# XQ8266.net
KiCad netlist of a schematic drawn in EasyEDA Pro
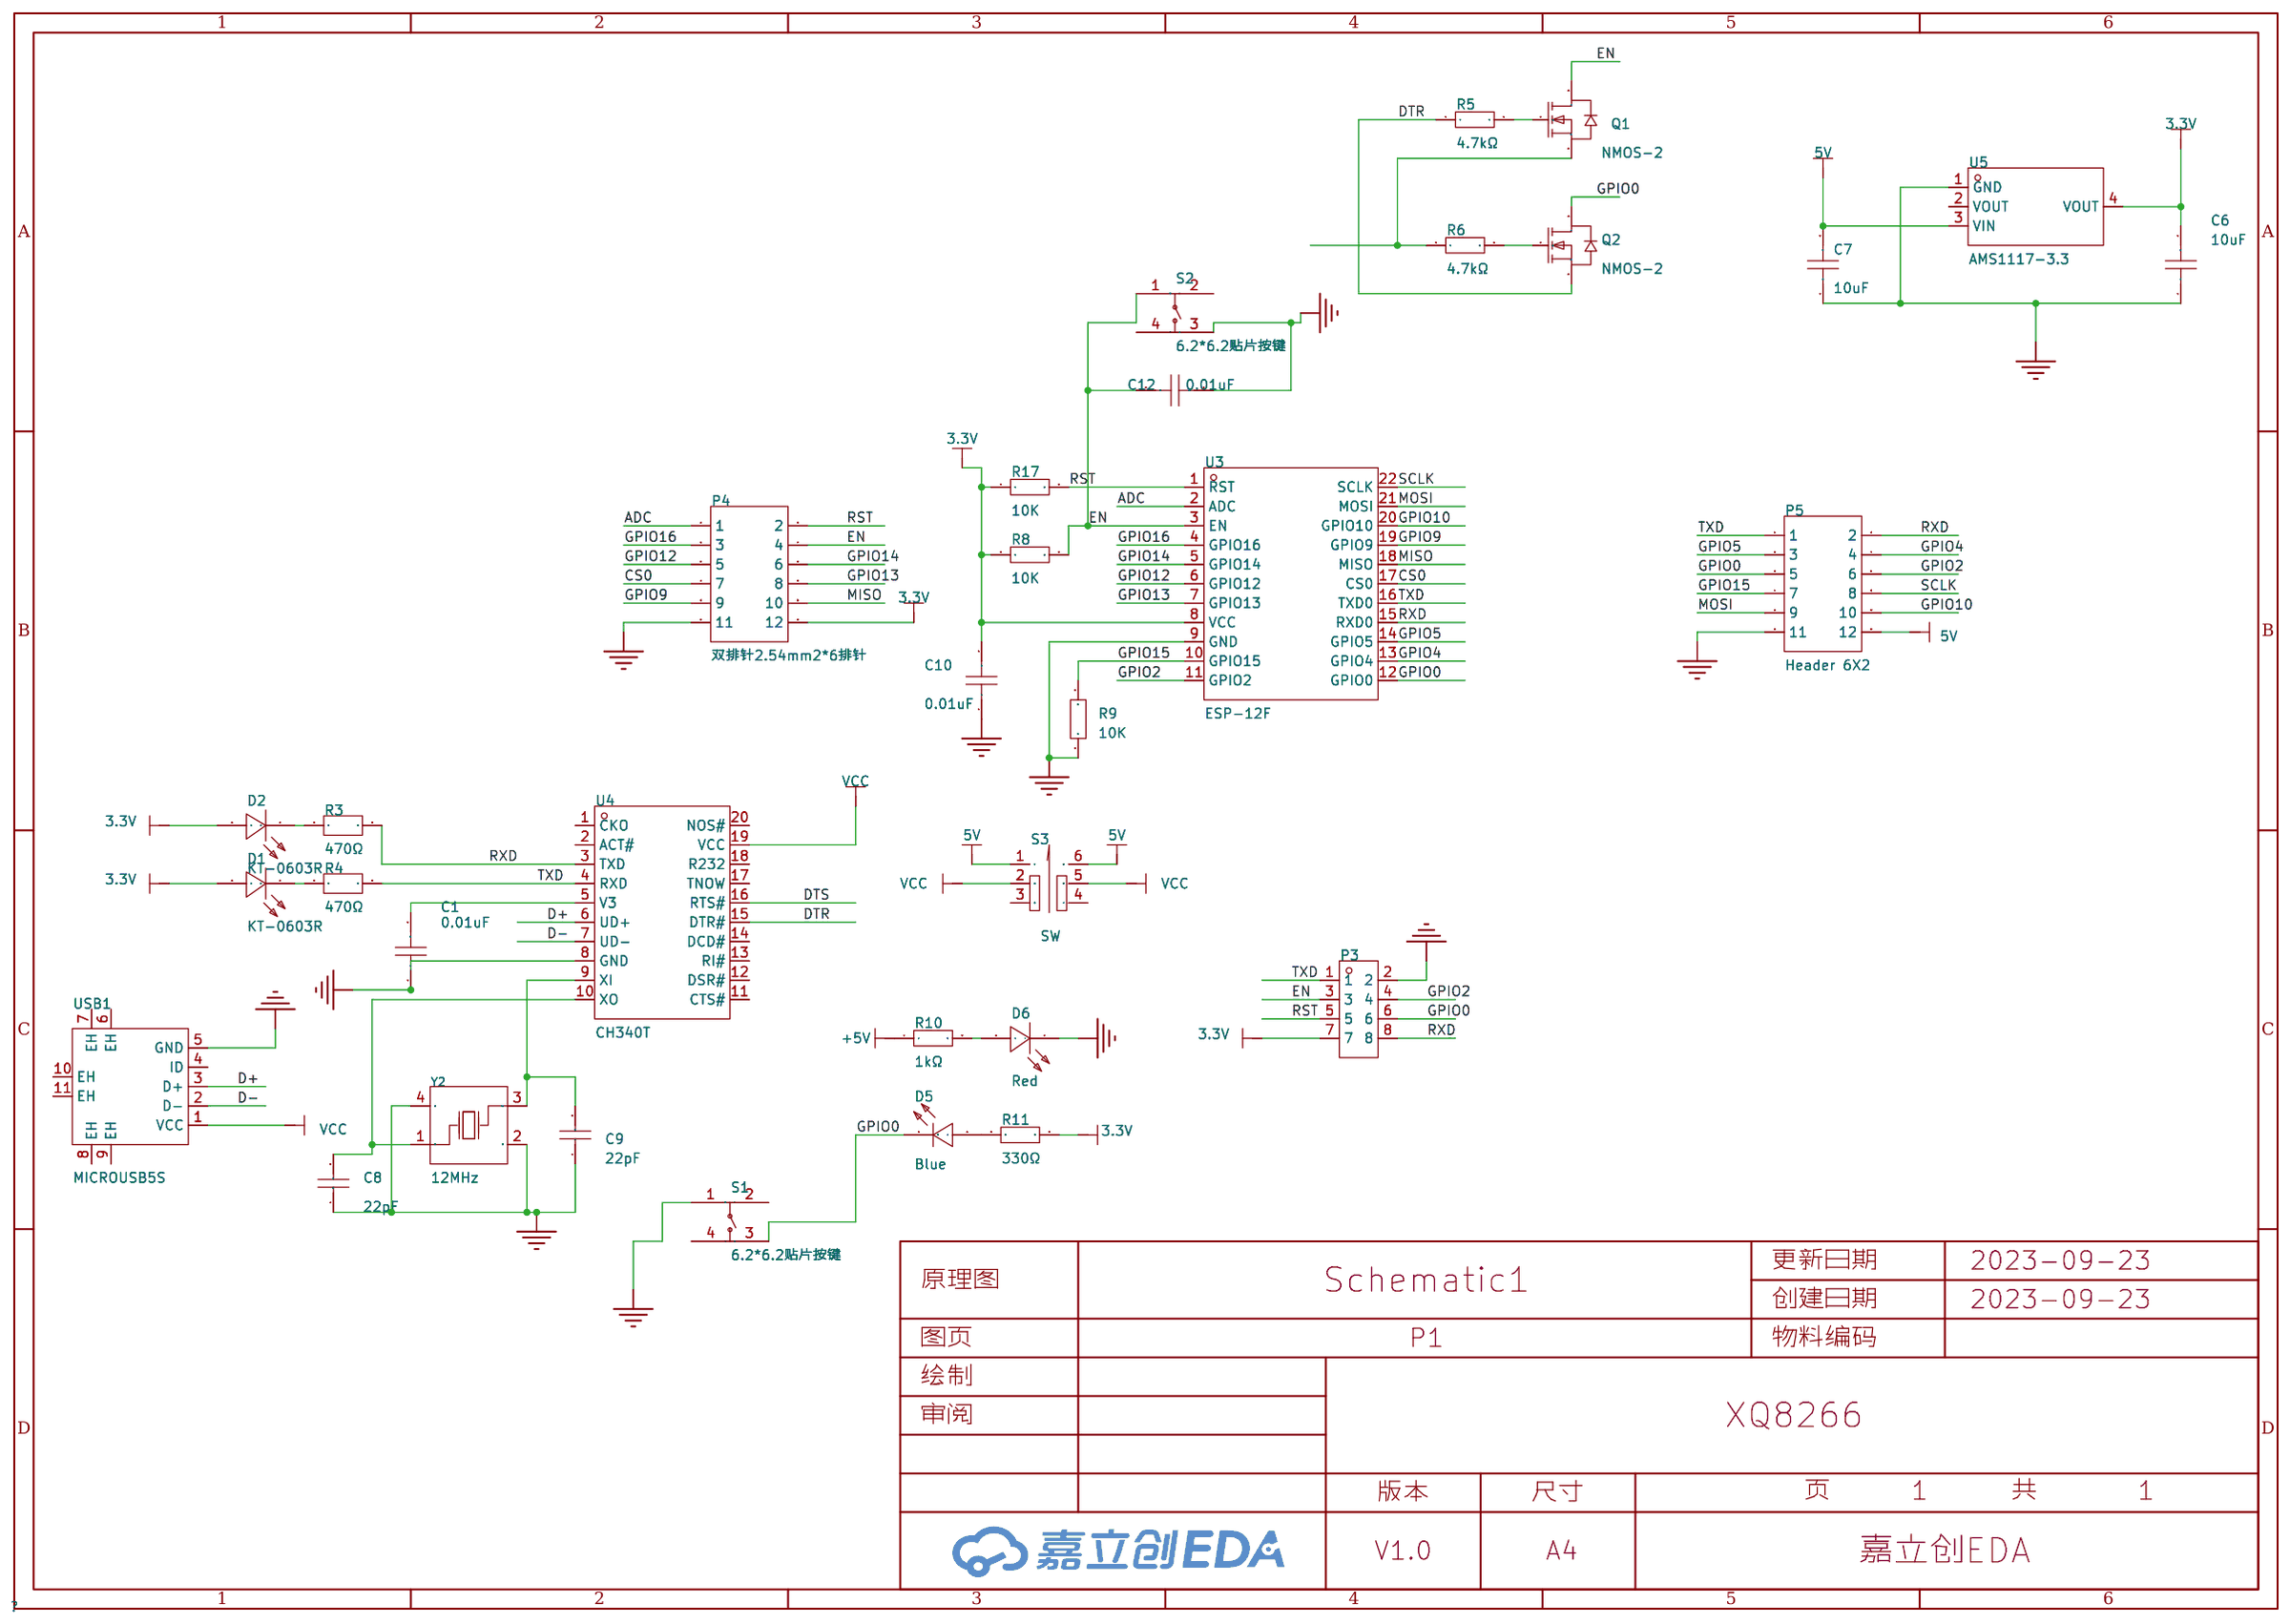
[diagram p0: schematic sheet]

(export (version "E")
  (design (tool "Eeschema 10.0.6"))
  (components
    (comp (ref "C1")
      (value "0.01uF")
      (footprint "easyedapro:C0603")
      (description "精度:±10%;")
      (libsource (lib "easyedapro") (part "CT41-0603-2X1-50V-0.01UF-K(N)"))
    )
    (comp (ref "C6")
      (value "10uF")
      (footprint "easyedapro:C0603")
      (description "容值:10uF;精度:±20%;额定电压:16V;材质(温度系数):-;")
      (fields (field (name "Manufacturer") "SAMSUNG(三星)"))
      (libsource (lib "easyedapro") (part "10UF"))
    )
    (comp (ref "C7")
      (value "10uF")
      (footprint "easyedapro:C0603")
      (description "容值:10uF;精度:±20%;额定电压:16V;材质(温度系数):-;")
      (fields (field (name "Manufacturer") "SAMSUNG(三星)"))
      (libsource (lib "easyedapro") (part "10UF"))
    )
    (comp (ref "C8")
      (value "22pF")
      (footprint "easyedapro:C0603")
      (description "容值:22pF;精度:±5%;额定电压:50V;材质(温度系数):C0G;")
      (fields
        (field (name "Manufacturer Part") "CL10C220JB8NNNC")
        (field (name "Manufacturer") "SAMSUNG(三星)")
      )
      (libsource (lib "easyedapro") (part "CL10C220JB8NNNC"))
    )
    (comp (ref "C9")
      (value "22pF")
      (footprint "easyedapro:C0603")
      (description "容值:22pF;精度:±5%;额定电压:50V;材质(温度系数):C0G;")
      (fields
        (field (name "Manufacturer Part") "CL10C220JB8NNNC")
        (field (name "Manufacturer") "SAMSUNG(三星)")
      )
      (libsource (lib "easyedapro") (part "CL10C220JB8NNNC"))
    )
    (comp (ref "C10")
      (value "0.01uF")
      (footprint "easyedapro:C0603")
      (description "精度:±10%;")
      (libsource (lib "easyedapro") (part "CT41-0603-2X1-50V-0.01UF-K(N)"))
    )
    (comp (ref "C12")
      (value "0.01uF")
      (footprint "easyedapro:C0603")
      (description "精度:±10%;")
      (libsource (lib "easyedapro") (part "CT41-0603-2X1-50V-0.01UF-K(N)"))
    )
    (comp (ref "D1")
      (value "KT-0603R")
      (footprint "easyedapro:LED0603-RD")
      (description "发光颜色:红灯;二极管配置:-;透镜颜色:-;主波长:-;色温:-;功率:-;发光角度:-;安装方式:-;工作温度:-40°C~+85°C;")
      (fields (field (name "Manufacturer") "KENTO"))
      (libsource (lib "easyedapro") (part "KT-0603R"))
    )
    (comp (ref "D2")
      (value "KT-0603R")
      (footprint "easyedapro:LED0603-RD")
      (description "发光颜色:红灯;二极管配置:-;透镜颜色:-;主波长:-;色温:-;功率:-;发光角度:-;安装方式:-;工作温度:-40°C~+85°C;")
      (fields (field (name "Manufacturer") "KENTO"))
      (libsource (lib "easyedapro") (part "KT-0603R"))
    )
    (comp (ref "D5")
      (value "Blue")
      (footprint "easyedapro:LED0603-FD_BLUE")
      (description "发光颜色:蓝灯;二极管配置:-;主波长:465nm~475nm;色温:-;功率:110mW;安装方式:-;")
      (fields (field (name "Manufacturer") "EVERLIGHT(亿光)"))
      (libsource (lib "easyedapro") (part "19-217/BHC-ZL1M2RY/3T"))
    )
    (comp (ref "D6")
      (value "Red")
      (footprint "easyedapro:LED0603-RD")
      (libsource (lib "easyedapro") (part "LTE-C9908-GD"))
    )
    (comp (ref "P3")
      (value "2.0排针 2*4p")
      (footprint "easyedapro:HDR-TH_8P-P2.00-V-M-R2-C4-S2.00")
      (libsource (lib "easyedapro") (part "2.0排针 2*4P"))
    )
    (comp (ref "P4")
      (value "双排针2.54mm2*6排针")
      (footprint "easyedapro:HDR-TH_12P-P2.54-V-M-R2-C6-S2.54")
      (libsource (lib "easyedapro") (part "Header-Male-2.54_2x6"))
    )
    (comp (ref "P5")
      (value "Header 6X2")
      (footprint "easyedapro:HDR-TH_12P-P2.54-V-M-R2-C6-S2.54")
      (libsource (lib "easyedapro") (part "Header-Male-2.54_2x6"))
    )
    (comp (ref "Q1")
      (value "NMOS-2")
      (footprint "easyedapro:SOT-323-3_L2.0-W1.3-P1.30-LS2.1-BR")
      (libsource (lib "easyedapro") (part "NMOS-2"))
    )
    (comp (ref "Q2")
      (value "NMOS-2")
      (footprint "easyedapro:SOT-323-3_L2.0-W1.3-P1.30-LS2.1-BR")
      (libsource (lib "easyedapro") (part "NMOS-2"))
    )
    (comp (ref "R3")
      (value "470Ω")
      (footprint "easyedapro:R0603")
      (description "阻值:470Ω;精度:±1%;功率:100mW;")
      (fields
        (field (name "Manufacturer Part") "CR0603F470RP05Z")
        (field (name "Manufacturer") "EVER OHMS(天二科技)")
      )
      (libsource (lib "easyedapro") (part "CR0603F470RP05Z"))
    )
    (comp (ref "R4")
      (value "470Ω")
      (footprint "easyedapro:R0603")
      (description "阻值:470Ω;精度:±1%;功率:100mW;")
      (fields
        (field (name "Manufacturer Part") "CR0603F470RP05Z")
        (field (name "Manufacturer") "EVER OHMS(天二科技)")
      )
      (libsource (lib "easyedapro") (part "CR0603F470RP05Z"))
    )
    (comp (ref "R5")
      (value "4.7kΩ")
      (footprint "easyedapro:R0603")
      (description "电阻类型:厚膜电阻;阻值:4.7kΩ;精度:±1%;功率:100mW;")
      (fields
        (field (name "Manufacturer Part") "0603WAF4701T5E")
        (field (name "Manufacturer") "UNI-ROYAL(厚声)")
      )
      (libsource (lib "easyedapro") (part "0603WAF4701T5E"))
    )
    (comp (ref "R6")
      (value "4.7kΩ")
      (footprint "easyedapro:R0603")
      (description "电阻类型:厚膜电阻;阻值:4.7kΩ;精度:±1%;功率:100mW;")
      (fields
        (field (name "Manufacturer Part") "0603WAF4701T5E")
        (field (name "Manufacturer") "UNI-ROYAL(厚声)")
      )
      (libsource (lib "easyedapro") (part "0603WAF4701T5E"))
    )
    (comp (ref "R8")
      (value "10K")
      (footprint "easyedapro:R0603")
      (description "电阻类型:厚膜电阻;阻值:10kΩ;精度:±1%;功率:100mW;")
      (fields
        (field (name "Manufacturer Part") "0603WAF1002T5E")
        (field (name "Manufacturer") "UNI-ROYAL(厚声)")
      )
      (libsource (lib "easyedapro") (part "0603WAF1002T5E"))
    )
    (comp (ref "R9")
      (value "10K")
      (footprint "easyedapro:R0603")
      (description "电阻类型:厚膜电阻;阻值:10kΩ;精度:±1%;功率:100mW;")
      (fields
        (field (name "Manufacturer Part") "0603WAF1002T5E")
        (field (name "Manufacturer") "UNI-ROYAL(厚声)")
      )
      (libsource (lib "easyedapro") (part "0603WAF1002T5E"))
    )
    (comp (ref "R10")
      (value "1kΩ")
      (footprint "easyedapro:R0603")
      (description "电阻类型:厚膜电阻;阻值:1kΩ;精度:±1%;功率:100mW;")
      (fields
        (field (name "Manufacturer Part") "0603WAF1001T5E")
        (field (name "Manufacturer") "UNI-ROYAL(厚声)")
      )
      (libsource (lib "easyedapro") (part "0603WAF1001T5E"))
    )
    (comp (ref "R11")
      (value "330Ω")
      (footprint "easyedapro:R0805")
      (description "电阻类型:厚膜电阻;阻值:330Ω;精度:±1%;功率:125mW;")
      (fields
        (field (name "Manufacturer Part") "0805W8F3300T5E")
        (field (name "Manufacturer") "UNI-ROYAL(厚声)")
      )
      (libsource (lib "easyedapro") (part "0805W8F3300T5E"))
    )
    (comp (ref "R17")
      (value "10K")
      (footprint "easyedapro:R0603")
      (description "电阻类型:厚膜电阻;阻值:10kΩ;精度:±1%;功率:100mW;")
      (fields
        (field (name "Manufacturer Part") "0603WAF1002T5E")
        (field (name "Manufacturer") "UNI-ROYAL(厚声)")
      )
      (libsource (lib "easyedapro") (part "0603WAF1002T5E"))
    )
    (comp (ref "S1")
      (value "6.2*6.2贴片按键")
      (footprint "easyedapro:SW-SMD_4P-L6.2-W6.2-P4.00-LS9.5-TL")
      (libsource (lib "easyedapro") (part "6.2*6.2贴片按键"))
    )
    (comp (ref "S2")
      (value "6.2*6.2贴片按键")
      (footprint "easyedapro:SW-SMD_4P-L6.2-W6.2-P4.00-LS9.5-TL")
      (libsource (lib "easyedapro") (part "6.2*6.2贴片按键"))
    )
    (comp (ref "S3")
      (value "SW")
      (footprint "easyedapro:SW-TH_6P-L5.8-W5.8-P2.00-LS4.5-TR")
      (description "耐温260度")
      (libsource (lib "easyedapro") (part "Self-locking switch 5.8ZWhite and white260G"))
    )
    (comp (ref "U3")
      (value "ESP-12F")
      (footprint "easyedapro:WIFIM-SMD_ESP-12F-ESP8266MOD")
      (description "频率:2.4GHz;发射功率:16dBm;核心处理器:ESP8266;天线形式:PCB 板载天线;接收灵敏度:-90dBm;")
      (fields
        (field (name "Manufacturer Part") "ESP-12F(ESP8266MOD)")
        (field (name "Manufacturer") "Ai-Thinker(安信可)")
      )
      (libsource (lib "easyedapro") (part "ESP-12F(ESP8266MOD)"))
    )
    (comp (ref "U4")
      (value "CH340T")
      (footprint "easyedapro:SSOP-20_L7.5-W5.2-P0.65-LS8.0-BL")
      (description "应用功能:收发器;接口协议:USB 2.0;数据速率:2Mbps;供电电压:3.3V；5V;")
      (fields (field (name "Manufacturer") "WCH(南京沁恒)"))
      (libsource (lib "easyedapro") (part "CH340T"))
    )
    (comp (ref "U5")
      (value "AMS1117-3.3")
      (footprint "easyedapro:SOT-223-3_L6.5-W3.4-P2.30-LS7.0-BR")
      (description "输出类型:固定;输出极性:正;最大输入电压:-;输出电压:3.3V;输出电流:1A;电源纹波抑制比(PSRR):72dB@(120Hz);")
      (fields (field (name "Manufacturer") "AMS"))
      (libsource (lib "easyedapro") (part "AMS1117-3.3"))
    )
    (comp (ref "USB1")
      (value "MICROUSB5S")
      (footprint "easyedapro:MICRO-USB_MICRO-USB-5S")
      (libsource (lib "easyedapro") (part "MICROUSB5S"))
    )
    (comp (ref "Y2")
      (value "12MHz")
      (footprint "easyedapro:OSC-SMD_4P-L3.2-W2.5-BL")
      (description "频率:12MHz;频率公差:±10ppm;负载电容:20pF;")
      (fields (field (name "Manufacturer Part") "X322512MSB4SI") (field (name "Manufacturer") "YXC(扬兴晶振)"))
      (libsource (lib "easyedapro") (part "X322512MSB4SI"))
    )
  )
  (nets
    (net (code "1") (name "+5V") (class "Default")
      (node (ref "R10") (pin "1") (pinfunction "1_1") (pintype "input"))
    )
    (net (code "2") (name "/ADC") (class "Default")
      (node (ref "P4") (pin "1") (pinfunction "1_1") (pintype "input"))
      (node (ref "U3") (pin "2") (pinfunction "ADC_2") (pintype "input"))
    )
    (net (code "3") (name "/CS0") (class "Default")
      (node (ref "P4") (pin "7") (pinfunction "7_7") (pintype "input"))
      (node (ref "U3") (pin "17") (pinfunction "CS0_17") (pintype "input"))
    )
    (net (code "4") (name "/D+") (class "Default")
      (node (ref "U4") (pin "6") (pinfunction "UD+_6") (pintype "input"))
      (node (ref "USB1") (pin "3") (pinfunction "D+_3") (pintype "input"))
    )
    (net (code "5") (name "/D-") (class "Default")
      (node (ref "U4") (pin "7") (pinfunction "UD-_7") (pintype "input"))
      (node (ref "USB1") (pin "2") (pinfunction "D-_2") (pintype "input"))
    )
    (net (code "6") (name "/DTR") (class "Default")
      (node (ref "Q2") (pin "2") (pinfunction "S_2") (pintype "input"))
      (node (ref "R5") (pin "1") (pinfunction "1_1") (pintype "input"))
      (node (ref "U4") (pin "15") (pinfunction "DTR#_15") (pintype "input"))
    )
    (net (code "7") (name "/DTS") (class "Default")
      (node (ref "U4") (pin "16") (pinfunction "RTS#_16") (pintype "input"))
    )
    (net (code "8") (name "/EN") (class "Default")
      (node (ref "C12") (pin "2") (pinfunction "2_2") (pintype "input"))
      (node (ref "P3") (pin "3") (pinfunction "3_3") (pintype "input"))
      (node (ref "P4") (pin "4") (pinfunction "4_4") (pintype "input"))
      (node (ref "Q1") (pin "3") (pinfunction "D_3") (pintype "input"))
      (node (ref "R8") (pin "2") (pinfunction "2_2") (pintype "input"))
      (node (ref "S2") (pin "1") (pinfunction "1_1") (pintype "input"))
      (node (ref "U3") (pin "3") (pinfunction "EN_3") (pintype "input"))
    )
    (net (code "9") (name "/GPIO0") (class "Default")
      (node (ref "D5") (pin "1") (pinfunction "C_1") (pintype "input"))
      (node (ref "P3") (pin "6") (pinfunction "6_6") (pintype "input"))
      (node (ref "P5") (pin "5") (pinfunction "5_5") (pintype "input"))
      (node (ref "Q2") (pin "3") (pinfunction "D_3") (pintype "input"))
      (node (ref "S1") (pin "3") (pinfunction "3_3") (pintype "input"))
      (node (ref "U3") (pin "12") (pinfunction "GPIO0_12") (pintype "input"))
    )
    (net (code "10") (name "/GPIO2") (class "Default")
      (node (ref "P3") (pin "4") (pinfunction "4_4") (pintype "input"))
      (node (ref "P5") (pin "6") (pinfunction "6_6") (pintype "input"))
      (node (ref "U3") (pin "11") (pinfunction "GPIO2_11") (pintype "input"))
    )
    (net (code "11") (name "/GPIO4") (class "Default")
      (node (ref "P5") (pin "4") (pinfunction "4_4") (pintype "input"))
      (node (ref "U3") (pin "13") (pinfunction "GPIO4_13") (pintype "input"))
    )
    (net (code "12") (name "/GPIO5") (class "Default")
      (node (ref "P5") (pin "3") (pinfunction "3_3") (pintype "input"))
      (node (ref "U3") (pin "14") (pinfunction "GPIO5_14") (pintype "input"))
    )
    (net (code "13") (name "/GPIO9") (class "Default")
      (node (ref "P4") (pin "9") (pinfunction "9_9") (pintype "input"))
      (node (ref "U3") (pin "19") (pinfunction "GPIO9_19") (pintype "input"))
    )
    (net (code "14") (name "/GPIO10") (class "Default")
      (node (ref "P5") (pin "10") (pinfunction "10_10") (pintype "input"))
      (node (ref "U3") (pin "20") (pinfunction "GPIO10_20") (pintype "input"))
    )
    (net (code "15") (name "/GPIO12") (class "Default")
      (node (ref "P4") (pin "5") (pinfunction "5_5") (pintype "input"))
      (node (ref "U3") (pin "6") (pinfunction "GPIO12_6") (pintype "input"))
    )
    (net (code "16") (name "/GPIO13") (class "Default")
      (node (ref "P4") (pin "8") (pinfunction "8_8") (pintype "input"))
      (node (ref "U3") (pin "7") (pinfunction "GPIO13_7") (pintype "input"))
    )
    (net (code "17") (name "/GPIO14") (class "Default")
      (node (ref "P4") (pin "6") (pinfunction "6_6") (pintype "input"))
      (node (ref "U3") (pin "5") (pinfunction "GPIO14_5") (pintype "input"))
    )
    (net (code "18") (name "/GPIO15") (class "Default")
      (node (ref "P5") (pin "7") (pinfunction "7_7") (pintype "input"))
      (node (ref "R9") (pin "2") (pinfunction "2_2") (pintype "input"))
      (node (ref "U3") (pin "10") (pinfunction "GPIO15_10") (pintype "input"))
    )
    (net (code "19") (name "/GPIO16") (class "Default")
      (node (ref "P4") (pin "3") (pinfunction "3_3") (pintype "input"))
      (node (ref "U3") (pin "4") (pinfunction "GPIO16_4") (pintype "input"))
    )
    (net (code "20") (name "/MISO") (class "Default")
      (node (ref "P4") (pin "10") (pinfunction "10_10") (pintype "input"))
      (node (ref "U3") (pin "18") (pinfunction "MISO_18") (pintype "input"))
    )
    (net (code "21") (name "/MOSI") (class "Default")
      (node (ref "P5") (pin "9") (pinfunction "9_9") (pintype "input"))
      (node (ref "U3") (pin "21") (pinfunction "MOSI_21") (pintype "input"))
    )
    (net (code "22") (name "/RST") (class "Default")
      (node (ref "P3") (pin "5") (pinfunction "5_5") (pintype "input"))
      (node (ref "P4") (pin "2") (pinfunction "2_2") (pintype "input"))
      (node (ref "R17") (pin "2") (pinfunction "2_2") (pintype "input"))
      (node (ref "U3") (pin "1") (pinfunction "RST_1") (pintype "input"))
    )
    (net (code "23") (name "/RXD") (class "Default")
      (node (ref "P3") (pin "8") (pinfunction "8_8") (pintype "input"))
      (node (ref "P5") (pin "2") (pinfunction "2_2") (pintype "input"))
      (node (ref "R3") (pin "2") (pinfunction "2_2") (pintype "input"))
      (node (ref "U3") (pin "15") (pinfunction "RXD0_15") (pintype "input"))
      (node (ref "U4") (pin "3") (pinfunction "TXD_3") (pintype "input"))
    )
    (net (code "24") (name "/SCLK") (class "Default")
      (node (ref "P5") (pin "8") (pinfunction "8_8") (pintype "input"))
      (node (ref "U3") (pin "22") (pinfunction "SCLK_22") (pintype "input"))
    )
    (net (code "25") (name "/TXD") (class "Default")
      (node (ref "P3") (pin "1") (pinfunction "1_1") (pintype "input"))
      (node (ref "P5") (pin "1") (pinfunction "1_1") (pintype "input"))
      (node (ref "R4") (pin "2") (pinfunction "2_2") (pintype "input"))
      (node (ref "U3") (pin "16") (pinfunction "TXD0_16") (pintype "input"))
      (node (ref "U4") (pin "4") (pinfunction "RXD_4") (pintype "input"))
    )
    (net (code "26") (name "3.3V") (class "Default")
      (node (ref "C10") (pin "2") (pinfunction "2_2") (pintype "input"))
      (node (ref "C6") (pin "2") (pinfunction "2_2") (pintype "input"))
      (node (ref "D1") (pin "2") (pinfunction "A_2") (pintype "input"))
      (node (ref "D2") (pin "2") (pinfunction "A_2") (pintype "input"))
      (node (ref "P3") (pin "7") (pinfunction "7_7") (pintype "input"))
      (node (ref "P4") (pin "12") (pinfunction "12_12") (pintype "input"))
      (node (ref "R11") (pin "2") (pinfunction "2_2") (pintype "input"))
      (node (ref "R17") (pin "1") (pinfunction "1_1") (pintype "input"))
      (node (ref "R8") (pin "1") (pinfunction "1_1") (pintype "input"))
      (node (ref "U3") (pin "8") (pinfunction "VCC_8") (pintype "input"))
      (node (ref "U5") (pin "4") (pinfunction "VOUT_4") (pintype "input"))
    )
    (net (code "27") (name "5V") (class "Default")
      (node (ref "C7") (pin "2") (pinfunction "2_2") (pintype "input"))
      (node (ref "P5") (pin "12") (pinfunction "12_12") (pintype "input"))
      (node (ref "S3") (pin "1") (pinfunction "1_1") (pintype "input"))
      (node (ref "S3") (pin "6") (pinfunction "6_6") (pintype "input"))
      (node (ref "U5") (pin "3") (pinfunction "VIN_3") (pintype "input"))
    )
    (net (code "28") (name "GND") (class "Default")
      (node (ref "C1") (pin "1") (pinfunction "1_1") (pintype "input"))
      (node (ref "C10") (pin "1") (pinfunction "1_1") (pintype "input"))
      (node (ref "C12") (pin "1") (pinfunction "1_1") (pintype "input"))
      (node (ref "C6") (pin "1") (pinfunction "1_1") (pintype "input"))
      (node (ref "C7") (pin "1") (pinfunction "1_1") (pintype "input"))
      (node (ref "C8") (pin "1") (pinfunction "1_1") (pintype "input"))
      (node (ref "C9") (pin "1") (pinfunction "1_1") (pintype "input"))
      (node (ref "D6") (pin "1") (pinfunction "-_1") (pintype "input"))
      (node (ref "P3") (pin "2") (pinfunction "2_2") (pintype "input"))
      (node (ref "P4") (pin "11") (pinfunction "11_11") (pintype "input"))
      (node (ref "P5") (pin "11") (pinfunction "11_11") (pintype "input"))
      (node (ref "R9") (pin "1") (pinfunction "1_1") (pintype "input"))
      (node (ref "S1") (pin "1") (pinfunction "1_1") (pintype "input"))
      (node (ref "S2") (pin "3") (pinfunction "3_3") (pintype "input"))
      (node (ref "U3") (pin "9") (pinfunction "GND_9") (pintype "input"))
      (node (ref "U4") (pin "8") (pinfunction "GND_8") (pintype "input"))
      (node (ref "U5") (pin "1") (pinfunction "GND_1") (pintype "input"))
      (node (ref "USB1") (pin "5") (pinfunction "GND_5") (pintype "input"))
      (node (ref "Y2") (pin "2") (pinfunction "GND_2") (pintype "input"))
      (node (ref "Y2") (pin "4") (pinfunction "GND_4") (pintype "input"))
    )
    (net (code "29") (name "Net-(D1-K)") (class "Default")
      (node (ref "D1") (pin "1") (pinfunction "K_1") (pintype "input"))
      (node (ref "R4") (pin "1") (pinfunction "1_1") (pintype "input"))
    )
    (net (code "30") (name "Net-(D2-K)") (class "Default")
      (node (ref "D2") (pin "1") (pinfunction "K_1") (pintype "input"))
      (node (ref "R3") (pin "1") (pinfunction "1_1") (pintype "input"))
    )
    (net (code "31") (name "Net-(D5-A)") (class "Default")
      (node (ref "D5") (pin "2") (pinfunction "A_2") (pintype "input"))
      (node (ref "R11") (pin "1") (pinfunction "1_1") (pintype "input"))
    )
    (net (code "32") (name "Net-(D6-+)") (class "Default")
      (node (ref "D6") (pin "2") (pinfunction "+_2") (pintype "input"))
      (node (ref "R10") (pin "2") (pinfunction "2_2") (pintype "input"))
    )
    (net (code "33") (name "Net-(Q1-G)") (class "Default")
      (node (ref "Q1") (pin "1") (pinfunction "G_1") (pintype "input"))
      (node (ref "R5") (pin "2") (pinfunction "2_2") (pintype "input"))
    )
    (net (code "34") (name "Net-(Q1-S)") (class "Default")
      (node (ref "Q1") (pin "2") (pinfunction "S_2") (pintype "input"))
      (node (ref "R6") (pin "1") (pinfunction "1_1") (pintype "input"))
    )
    (net (code "35") (name "Net-(Q2-G)") (class "Default")
      (node (ref "Q2") (pin "1") (pinfunction "G_1") (pintype "input"))
      (node (ref "R6") (pin "2") (pinfunction "2_2") (pintype "input"))
    )
    (net (code "36") (name "Net-(U4-V3)") (class "Default")
      (node (ref "C1") (pin "2") (pinfunction "2_2") (pintype "input"))
      (node (ref "U4") (pin "5") (pinfunction "V3_5") (pintype "input"))
    )
    (net (code "37") (name "Net-(U4-XI)") (class "Default")
      (node (ref "C9") (pin "2") (pinfunction "2_2") (pintype "input"))
      (node (ref "U4") (pin "9") (pinfunction "XI_9") (pintype "input"))
      (node (ref "Y2") (pin "3") (pinfunction "OSC2_3") (pintype "input"))
    )
    (net (code "38") (name "Net-(U4-XO)") (class "Default")
      (node (ref "C8") (pin "2") (pinfunction "2_2") (pintype "input"))
      (node (ref "U4") (pin "10") (pinfunction "XO_10") (pintype "input"))
      (node (ref "Y2") (pin "1") (pinfunction "OSC1_1") (pintype "input"))
    )
    (net (code "39") (name "VCC") (class "Default")
      (node (ref "S3") (pin "2") (pinfunction "2_2") (pintype "input"))
      (node (ref "S3") (pin "5") (pinfunction "5_5") (pintype "input"))
      (node (ref "U4") (pin "19") (pinfunction "VCC_19") (pintype "input"))
      (node (ref "USB1") (pin "1") (pinfunction "VCC_1") (pintype "input"))
    )
    (net (code "40") (name "unconnected-(S1-Pad2)") (class "Default")
      (node (ref "S1") (pin "2") (pinfunction "2_2") (pintype "input"))
    )
    (net (code "41") (name "unconnected-(S1-Pad4)") (class "Default")
      (node (ref "S1") (pin "4") (pinfunction "4_4") (pintype "input"))
    )
    (net (code "42") (name "unconnected-(S2-Pad2)") (class "Default")
      (node (ref "S2") (pin "2") (pinfunction "2_2") (pintype "input"))
    )
    (net (code "43") (name "unconnected-(S2-Pad4)") (class "Default")
      (node (ref "S2") (pin "4") (pinfunction "4_4") (pintype "input"))
    )
    (net (code "44") (name "unconnected-(S3-Pad3)") (class "Default")
      (node (ref "S3") (pin "3") (pinfunction "3_3") (pintype "input"))
    )
    (net (code "45") (name "unconnected-(S3-Pad4)") (class "Default")
      (node (ref "S3") (pin "4") (pinfunction "4_4") (pintype "input"))
    )
    (net (code "46") (name "unconnected-(U4-ACT#-Pad2)") (class "Default")
      (node (ref "U4") (pin "2") (pinfunction "ACT#_2") (pintype "input"))
    )
    (net (code "47") (name "unconnected-(U4-CKO-Pad1)") (class "Default")
      (node (ref "U4") (pin "1") (pinfunction "CKO_1") (pintype "input"))
    )
    (net (code "48") (name "unconnected-(U4-CTS#-Pad11)") (class "Default")
      (node (ref "U4") (pin "11") (pinfunction "CTS#_11") (pintype "input"))
    )
    (net (code "49") (name "unconnected-(U4-DCD#-Pad14)") (class "Default")
      (node (ref "U4") (pin "14") (pinfunction "DCD#_14") (pintype "input"))
    )
    (net (code "50") (name "unconnected-(U4-DSR#-Pad12)") (class "Default")
      (node (ref "U4") (pin "12") (pinfunction "DSR#_12") (pintype "input"))
    )
    (net (code "51") (name "unconnected-(U4-NOS#-Pad20)") (class "Default")
      (node (ref "U4") (pin "20") (pinfunction "NOS#_20") (pintype "input"))
    )
    (net (code "52") (name "unconnected-(U4-R232-Pad18)") (class "Default")
      (node (ref "U4") (pin "18") (pinfunction "R232_18") (pintype "input"))
    )
    (net (code "53") (name "unconnected-(U4-RI#-Pad13)") (class "Default")
      (node (ref "U4") (pin "13") (pinfunction "RI#_13") (pintype "input"))
    )
    (net (code "54") (name "unconnected-(U4-TNOW-Pad17)") (class "Default")
      (node (ref "U4") (pin "17") (pinfunction "TNOW_17") (pintype "input"))
    )
    (net (code "55") (name "unconnected-(U5-VOUT-Pad2)") (class "Default")
      (node (ref "U5") (pin "2") (pinfunction "VOUT_2") (pintype "input"))
    )
    (net (code "56") (name "unconnected-(USB1-EH-Pad6)") (class "Default")
      (node (ref "USB1") (pin "6") (pinfunction "EH_6") (pintype "input"))
    )
    (net (code "57") (name "unconnected-(USB1-EH-Pad7)") (class "Default")
      (node (ref "USB1") (pin "7") (pinfunction "EH_7") (pintype "input"))
    )
    (net (code "58") (name "unconnected-(USB1-EH-Pad8)") (class "Default")
      (node (ref "USB1") (pin "8") (pinfunction "EH_8") (pintype "input"))
    )
    (net (code "59") (name "unconnected-(USB1-EH-Pad9)") (class "Default")
      (node (ref "USB1") (pin "9") (pinfunction "EH_9") (pintype "input"))
    )
    (net (code "60") (name "unconnected-(USB1-EH-Pad10)") (class "Default")
      (node (ref "USB1") (pin "10") (pinfunction "EH_10") (pintype "input"))
    )
    (net (code "61") (name "unconnected-(USB1-EH-Pad11)") (class "Default")
      (node (ref "USB1") (pin "11") (pinfunction "EH_11") (pintype "input"))
    )
    (net (code "62") (name "unconnected-(USB1-ID-Pad4)") (class "Default")
      (node (ref "USB1") (pin "4") (pinfunction "ID_4") (pintype "input"))
    )
  )
)
